# Fan_Block.net
KiCad netlist of a schematic drawn in Altium Designer
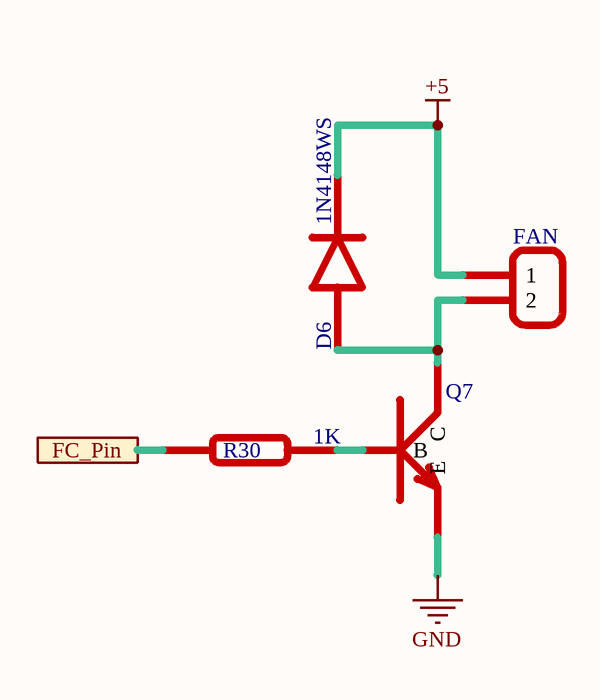
[diagram p0: Fan_Block.SchDoc]

(export (version "E")
  (design (tool "Eeschema 10.0.6"))
  (components
    (comp (ref "D6")
      (value "1N4148WS")
      (footprint "SMA")
      (description "Small Signal Diode")
      (libsource (lib "CTAI-Library") (part "1N4148WS"))
    )
    (comp (ref "H4")
      (value "FAN")
      (footprint "XH-2.54-2P")
      (description "Connector 2 Pole")
      (libsource (lib "CTAI-Library") (part "CONN-2P"))
    )
    (comp (ref "Q7")
      (value "S8050")
      (footprint "SOT-23")
      (description "NPN Transistors 0.5A Collector to Emitter 25V")
      (libsource (lib "CTAI-Library") (part "S8050"))
    )
    (comp (ref "R30")
      (value "1K")
      (footprint "R0603")
      (description "Resistor")
      (libsource (lib "CTAI-Library") (part "Resistor"))
    )
  )
  (nets
    (net (code "1") (name "+5") (class "Default")
      (node (ref "D6") (pin "K") (pinfunction "K_K") (pintype "passive"))
      (node (ref "H4") (pin "1") (pinfunction "1_1") (pintype "passive"))
    )
    (net (code "2") (name "/FC_Pin") (class "Default")
      (node (ref "R30") (pin "1") (pinfunction "1_1") (pintype "passive"))
    )
    (net (code "3") (name "GND") (class "Default")
      (node (ref "Q7") (pin "2") (pinfunction "E_2") (pintype "passive"))
    )
    (net (code "4") (name "Net-(Q7-B)") (class "Default")
      (node (ref "Q7") (pin "1") (pinfunction "B_1") (pintype "passive"))
      (node (ref "R30") (pin "2") (pinfunction "2_2") (pintype "passive"))
    )
    (net (code "5") (name "Net-(Q7-C)") (class "Default")
      (node (ref "D6") (pin "A") (pinfunction "A_A") (pintype "passive"))
      (node (ref "H4") (pin "2") (pinfunction "2_2") (pintype "passive"))
      (node (ref "Q7") (pin "3") (pinfunction "C_3") (pintype "passive"))
    )
  )
)
